# stm32-rs485-daughter.net
KiCad netlist of a schematic drawn in EAGLE
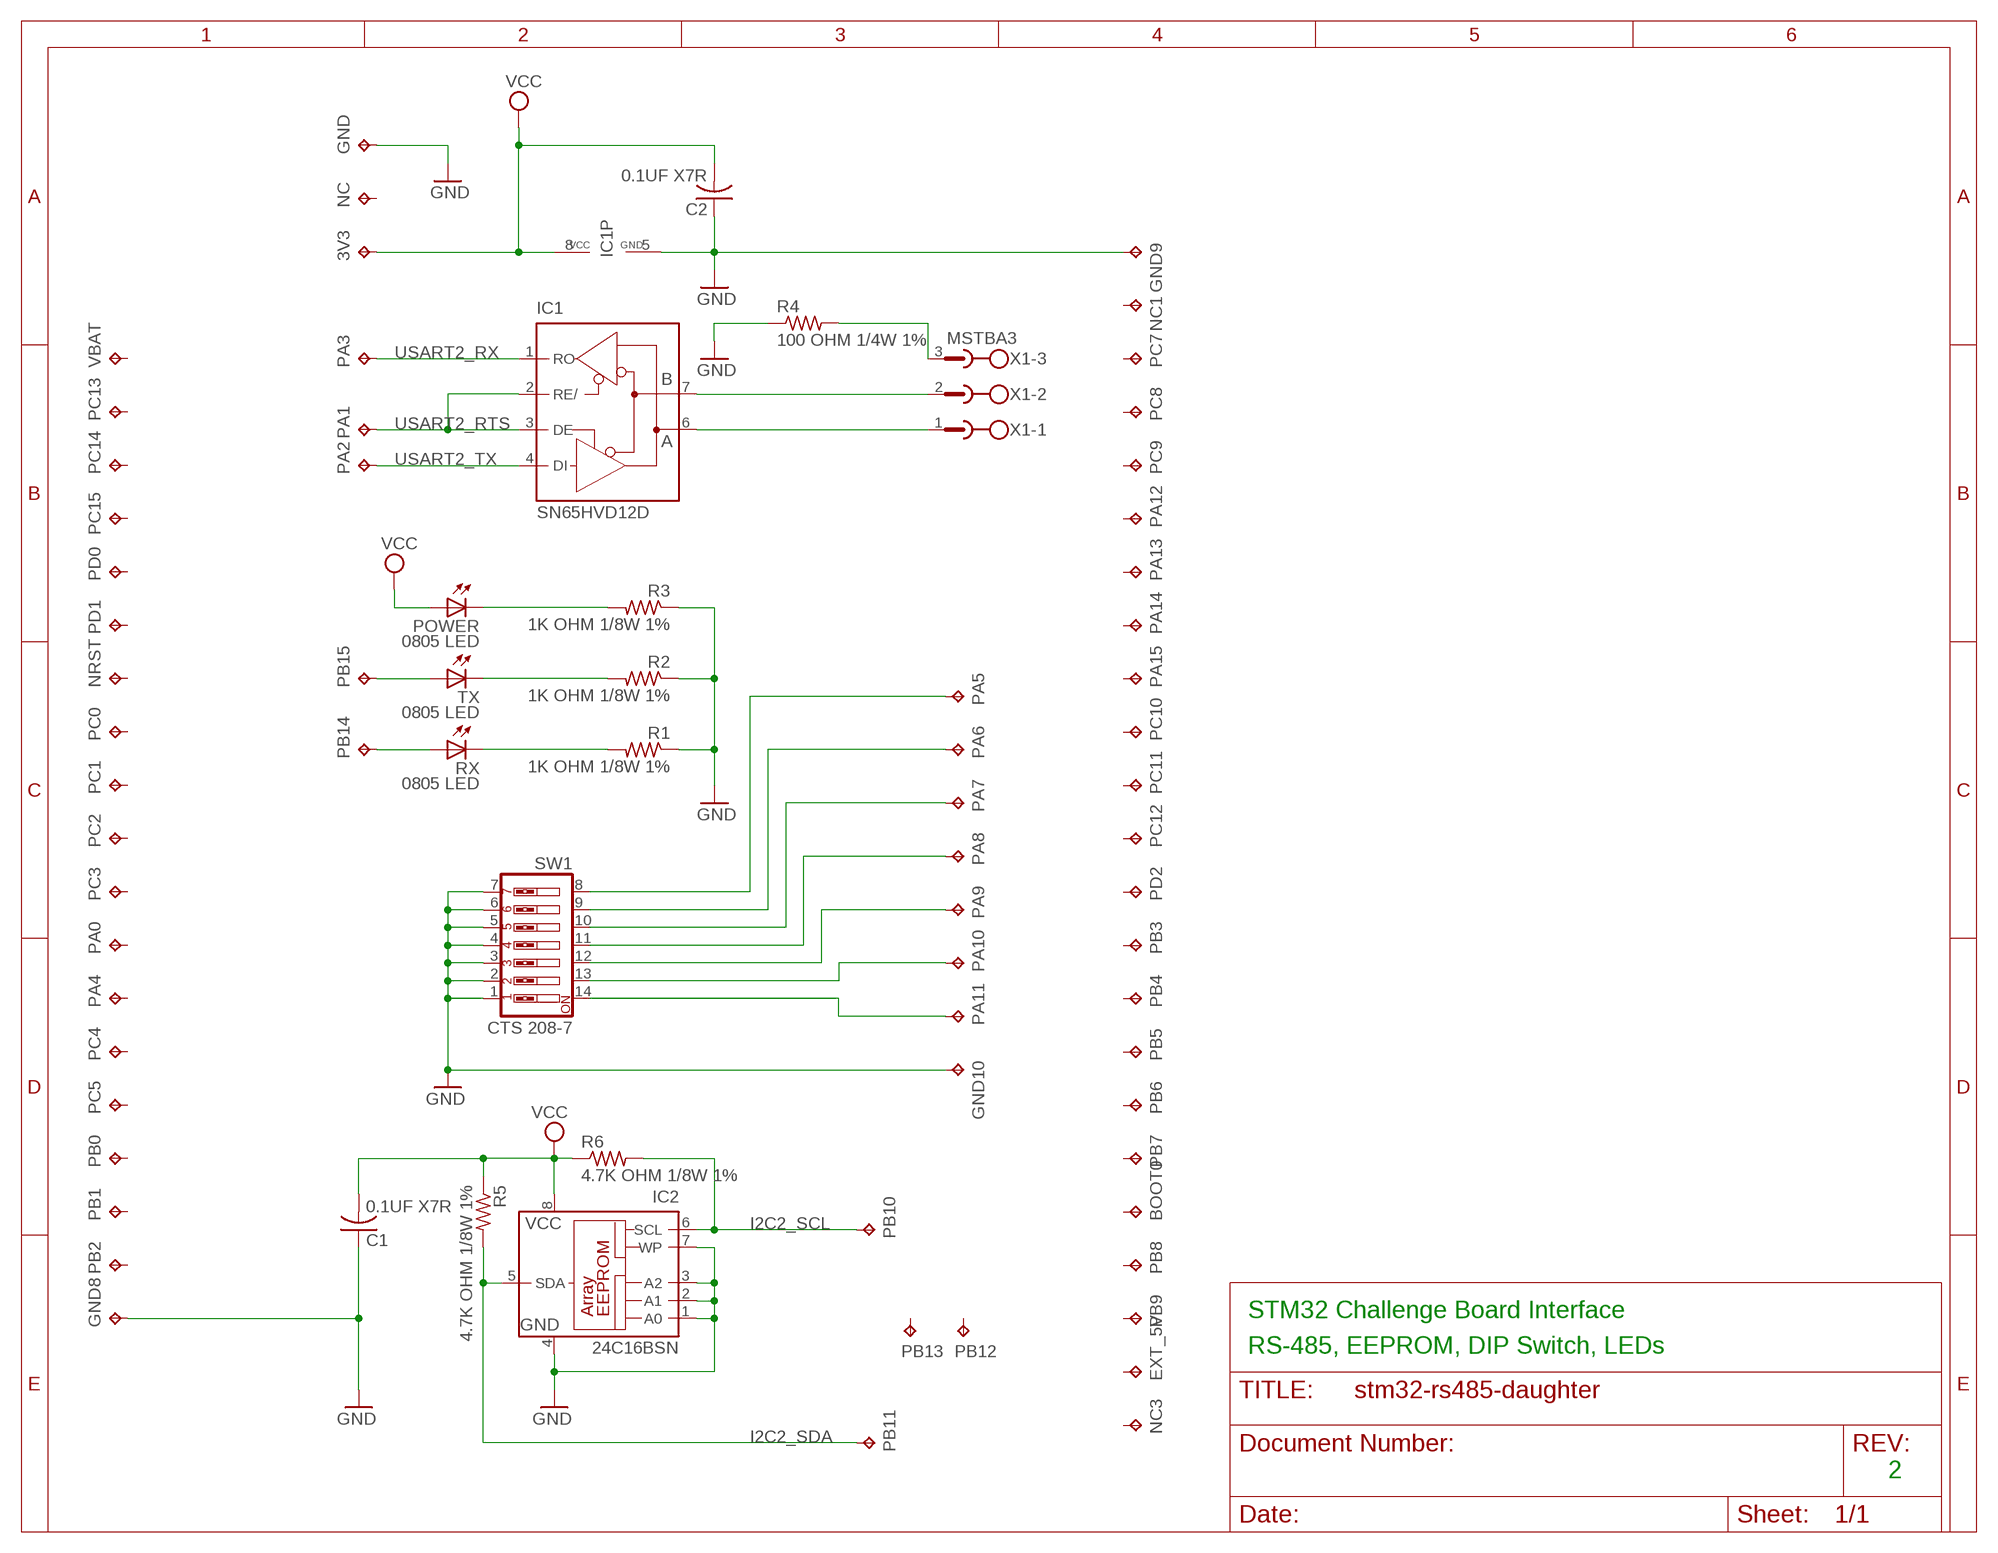
[diagram p0: schematic, sheet 1]

(export (version "E")
  (design (tool "Eeschema 10.0.6"))
  (components
    (comp (ref "3V3")
      (value "TPPAD1-13")
      (footprint "eagle-import:P1-13")
      (libsource (lib "eagle-import") (part "TPPAD1-13"))
    )
    (comp (ref "BOOT0")
      (value "TPPAD1-13")
      (footprint "eagle-import:P1-13")
      (libsource (lib "eagle-import") (part "TPPAD1-13"))
    )
    (comp (ref "C1")
      (value "0.1UF X7R")
      (footprint "eagle-import:C0805")
      (libsource (lib "eagle-import") (part "C-USC0805"))
    )
    (comp (ref "C2")
      (value "0.1UF X7R")
      (footprint "eagle-import:C0805")
      (libsource (lib "eagle-import") (part "C-USC0805"))
    )
    (comp (ref "EXT_5V")
      (value "TPPAD1-13")
      (footprint "eagle-import:P1-13")
      (libsource (lib "eagle-import") (part "TPPAD1-13"))
    )
    (comp (ref "GND")
      (value "TPPAD1-13")
      (footprint "eagle-import:P1-13")
      (libsource (lib "eagle-import") (part "TPPAD1-13"))
    )
    (comp (ref "GND8")
      (value "TPPAD1-13")
      (footprint "eagle-import:P1-13")
      (libsource (lib "eagle-import") (part "TPPAD1-13"))
    )
    (comp (ref "GND9")
      (value "TPPAD1-13")
      (footprint "eagle-import:P1-13")
      (libsource (lib "eagle-import") (part "TPPAD1-13"))
    )
    (comp (ref "GND10")
      (value "TPPAD1-13")
      (footprint "eagle-import:P1-13")
      (libsource (lib "eagle-import") (part "TPPAD1-13"))
    )
    (comp (ref "IC1")
      (value "SN65HVD12D")
      (footprint "eagle-import:SO08")
      (libsource (lib "eagle-import") (part "MAX481CSA"))
    )
    (comp (ref "IC2")
      (value "24C16BSN")
      (footprint "eagle-import:SO-08")
      (libsource (lib "eagle-import") (part "24SNC16B"))
    )
    (comp (ref "NC")
      (value "TPPAD1-13")
      (footprint "eagle-import:P1-13")
      (libsource (lib "eagle-import") (part "TPPAD1-13"))
    )
    (comp (ref "NC1")
      (value "TPPAD1-13")
      (footprint "eagle-import:P1-13")
      (libsource (lib "eagle-import") (part "TPPAD1-13"))
    )
    (comp (ref "NC3")
      (value "TPPAD1-13")
      (footprint "eagle-import:P1-13")
      (libsource (lib "eagle-import") (part "TPPAD1-13"))
    )
    (comp (ref "NRST")
      (value "TPPAD1-13")
      (footprint "eagle-import:P1-13")
      (libsource (lib "eagle-import") (part "TPPAD1-13"))
    )
    (comp (ref "PA0")
      (value "TPPAD1-13")
      (footprint "eagle-import:P1-13")
      (libsource (lib "eagle-import") (part "TPPAD1-13"))
    )
    (comp (ref "PA1")
      (value "TPPAD1-13")
      (footprint "eagle-import:P1-13")
      (libsource (lib "eagle-import") (part "TPPAD1-13"))
    )
    (comp (ref "PA2")
      (value "TPPAD1-13")
      (footprint "eagle-import:P1-13")
      (libsource (lib "eagle-import") (part "TPPAD1-13"))
    )
    (comp (ref "PA3")
      (value "TPPAD1-13")
      (footprint "eagle-import:P1-13")
      (libsource (lib "eagle-import") (part "TPPAD1-13"))
    )
    (comp (ref "PA4")
      (value "TPPAD1-13")
      (footprint "eagle-import:P1-13")
      (libsource (lib "eagle-import") (part "TPPAD1-13"))
    )
    (comp (ref "PA5")
      (value "TPPAD1-13")
      (footprint "eagle-import:P1-13")
      (libsource (lib "eagle-import") (part "TPPAD1-13"))
    )
    (comp (ref "PA6")
      (value "TPPAD1-13")
      (footprint "eagle-import:P1-13")
      (libsource (lib "eagle-import") (part "TPPAD1-13"))
    )
    (comp (ref "PA7")
      (value "TPPAD1-13")
      (footprint "eagle-import:P1-13")
      (libsource (lib "eagle-import") (part "TPPAD1-13"))
    )
    (comp (ref "PA8")
      (value "TPPAD1-13")
      (footprint "eagle-import:P1-13")
      (libsource (lib "eagle-import") (part "TPPAD1-13"))
    )
    (comp (ref "PA9")
      (value "TPPAD1-13")
      (footprint "eagle-import:P1-13")
      (libsource (lib "eagle-import") (part "TPPAD1-13"))
    )
    (comp (ref "PA10")
      (value "TPPAD1-13")
      (footprint "eagle-import:P1-13")
      (libsource (lib "eagle-import") (part "TPPAD1-13"))
    )
    (comp (ref "PA11")
      (value "TPPAD1-13")
      (footprint "eagle-import:P1-13")
      (libsource (lib "eagle-import") (part "TPPAD1-13"))
    )
    (comp (ref "PA12")
      (value "TPPAD1-13")
      (footprint "eagle-import:P1-13")
      (libsource (lib "eagle-import") (part "TPPAD1-13"))
    )
    (comp (ref "PA13")
      (value "TPPAD1-13")
      (footprint "eagle-import:P1-13")
      (libsource (lib "eagle-import") (part "TPPAD1-13"))
    )
    (comp (ref "PA14")
      (value "TPPAD1-13")
      (footprint "eagle-import:P1-13")
      (libsource (lib "eagle-import") (part "TPPAD1-13"))
    )
    (comp (ref "PA15")
      (value "TPPAD1-13")
      (footprint "eagle-import:P1-13")
      (libsource (lib "eagle-import") (part "TPPAD1-13"))
    )
    (comp (ref "PB0")
      (value "TPPAD1-13")
      (footprint "eagle-import:P1-13")
      (libsource (lib "eagle-import") (part "TPPAD1-13"))
    )
    (comp (ref "PB1")
      (value "TPPAD1-13")
      (footprint "eagle-import:P1-13")
      (libsource (lib "eagle-import") (part "TPPAD1-13"))
    )
    (comp (ref "PB2")
      (value "TPPAD1-13")
      (footprint "eagle-import:P1-13")
      (libsource (lib "eagle-import") (part "TPPAD1-13"))
    )
    (comp (ref "PB3")
      (value "TPPAD1-13")
      (footprint "eagle-import:P1-13")
      (libsource (lib "eagle-import") (part "TPPAD1-13"))
    )
    (comp (ref "PB4")
      (value "TPPAD1-13")
      (footprint "eagle-import:P1-13")
      (libsource (lib "eagle-import") (part "TPPAD1-13"))
    )
    (comp (ref "PB5")
      (value "TPPAD1-13")
      (footprint "eagle-import:P1-13")
      (libsource (lib "eagle-import") (part "TPPAD1-13"))
    )
    (comp (ref "PB6")
      (value "TPPAD1-13")
      (footprint "eagle-import:P1-13")
      (libsource (lib "eagle-import") (part "TPPAD1-13"))
    )
    (comp (ref "PB7")
      (value "TPPAD1-13")
      (footprint "eagle-import:P1-13")
      (libsource (lib "eagle-import") (part "TPPAD1-13"))
    )
    (comp (ref "PB8")
      (value "TPPAD1-13")
      (footprint "eagle-import:P1-13")
      (libsource (lib "eagle-import") (part "TPPAD1-13"))
    )
    (comp (ref "PB9")
      (value "TPPAD1-13")
      (footprint "eagle-import:P1-13")
      (libsource (lib "eagle-import") (part "TPPAD1-13"))
    )
    (comp (ref "PB10")
      (value "TPPAD1-13")
      (footprint "eagle-import:P1-13")
      (libsource (lib "eagle-import") (part "TPPAD1-13"))
    )
    (comp (ref "PB11")
      (value "TPPAD1-13")
      (footprint "eagle-import:P1-13")
      (libsource (lib "eagle-import") (part "TPPAD1-13"))
    )
    (comp (ref "PB12")
      (value "TPPAD1-13")
      (footprint "eagle-import:P1-13")
      (libsource (lib "eagle-import") (part "TPPAD1-13"))
    )
    (comp (ref "PB13")
      (value "TPPAD1-13")
      (footprint "eagle-import:P1-13")
      (libsource (lib "eagle-import") (part "TPPAD1-13"))
    )
    (comp (ref "PB14")
      (value "TPPAD1-13")
      (footprint "eagle-import:P1-13")
      (libsource (lib "eagle-import") (part "TPPAD1-13"))
    )
    (comp (ref "PB15")
      (value "TPPAD1-13")
      (footprint "eagle-import:P1-13")
      (libsource (lib "eagle-import") (part "TPPAD1-13"))
    )
    (comp (ref "PC0")
      (value "TPPAD1-13")
      (footprint "eagle-import:P1-13")
      (libsource (lib "eagle-import") (part "TPPAD1-13"))
    )
    (comp (ref "PC1")
      (value "TPPAD1-13")
      (footprint "eagle-import:P1-13")
      (libsource (lib "eagle-import") (part "TPPAD1-13"))
    )
    (comp (ref "PC2")
      (value "TPPAD1-13")
      (footprint "eagle-import:P1-13")
      (libsource (lib "eagle-import") (part "TPPAD1-13"))
    )
    (comp (ref "PC3")
      (value "TPPAD1-13")
      (footprint "eagle-import:P1-13")
      (libsource (lib "eagle-import") (part "TPPAD1-13"))
    )
    (comp (ref "PC4")
      (value "TPPAD1-13")
      (footprint "eagle-import:P1-13")
      (libsource (lib "eagle-import") (part "TPPAD1-13"))
    )
    (comp (ref "PC5")
      (value "TPPAD1-13")
      (footprint "eagle-import:P1-13")
      (libsource (lib "eagle-import") (part "TPPAD1-13"))
    )
    (comp (ref "PC7")
      (value "TPPAD1-13")
      (footprint "eagle-import:P1-13")
      (libsource (lib "eagle-import") (part "TPPAD1-13"))
    )
    (comp (ref "PC8")
      (value "TPPAD1-13")
      (footprint "eagle-import:P1-13")
      (libsource (lib "eagle-import") (part "TPPAD1-13"))
    )
    (comp (ref "PC9")
      (value "TPPAD1-13")
      (footprint "eagle-import:P1-13")
      (libsource (lib "eagle-import") (part "TPPAD1-13"))
    )
    (comp (ref "PC10")
      (value "TPPAD1-13")
      (footprint "eagle-import:P1-13")
      (libsource (lib "eagle-import") (part "TPPAD1-13"))
    )
    (comp (ref "PC11")
      (value "TPPAD1-13")
      (footprint "eagle-import:P1-13")
      (libsource (lib "eagle-import") (part "TPPAD1-13"))
    )
    (comp (ref "PC12")
      (value "TPPAD1-13")
      (footprint "eagle-import:P1-13")
      (libsource (lib "eagle-import") (part "TPPAD1-13"))
    )
    (comp (ref "PC13")
      (value "TPPAD1-13")
      (footprint "eagle-import:P1-13")
      (libsource (lib "eagle-import") (part "TPPAD1-13"))
    )
    (comp (ref "PC14")
      (value "TPPAD1-13")
      (footprint "eagle-import:P1-13")
      (libsource (lib "eagle-import") (part "TPPAD1-13"))
    )
    (comp (ref "PC15")
      (value "TPPAD1-13")
      (footprint "eagle-import:P1-13")
      (libsource (lib "eagle-import") (part "TPPAD1-13"))
    )
    (comp (ref "PD0")
      (value "TPPAD1-13")
      (footprint "eagle-import:P1-13")
      (libsource (lib "eagle-import") (part "TPPAD1-13"))
    )
    (comp (ref "PD1")
      (value "TPPAD1-13")
      (footprint "eagle-import:P1-13")
      (libsource (lib "eagle-import") (part "TPPAD1-13"))
    )
    (comp (ref "PD2")
      (value "TPPAD1-13")
      (footprint "eagle-import:P1-13")
      (libsource (lib "eagle-import") (part "TPPAD1-13"))
    )
    (comp (ref "POWER")
      (value "0805 LED")
      (footprint "eagle-import:CHIPLED_0805")
      (libsource (lib "eagle-import") (part "LEDCHIPLED_0805"))
    )
    (comp (ref "R1")
      (value "1K OHM 1/8W 1%")
      (footprint "eagle-import:R0805")
      (libsource (lib "eagle-import") (part "R-US_R0805"))
    )
    (comp (ref "R2")
      (value "1K OHM 1/8W 1%")
      (footprint "eagle-import:R0805")
      (libsource (lib "eagle-import") (part "R-US_R0805"))
    )
    (comp (ref "R3")
      (value "1K OHM 1/8W 1%")
      (footprint "eagle-import:R0805")
      (libsource (lib "eagle-import") (part "R-US_R0805"))
    )
    (comp (ref "R4")
      (value "100 OHM 1/4W 1%")
      (footprint "eagle-import:R1206")
      (libsource (lib "eagle-import") (part "R-US_R1206"))
    )
    (comp (ref "R5")
      (value "4.7K OHM 1/8W 1%")
      (footprint "eagle-import:R0805")
      (libsource (lib "eagle-import") (part "R-US_R0805"))
    )
    (comp (ref "R6")
      (value "4.7K OHM 1/8W 1%")
      (footprint "eagle-import:R0805")
      (libsource (lib "eagle-import") (part "R-US_R0805"))
    )
    (comp (ref "RX")
      (value "0805 LED")
      (footprint "eagle-import:CHIPLED_0805")
      (libsource (lib "eagle-import") (part "LEDCHIPLED_0805"))
    )
    (comp (ref "SW1")
      (value "CTS 208-7")
      (footprint "eagle-import:EDG-07")
      (libsource (lib "eagle-import") (part "SW_DIP-7"))
    )
    (comp (ref "TX")
      (value "0805 LED")
      (footprint "eagle-import:CHIPLED_0805")
      (libsource (lib "eagle-import") (part "LEDCHIPLED_0805"))
    )
    (comp (ref "VBAT")
      (value "TPPAD1-13")
      (footprint "eagle-import:P1-13")
      (libsource (lib "eagle-import") (part "TPPAD1-13"))
    )
    (comp (ref "X1")
      (value "MSTBA3")
      (footprint "eagle-import:MSTBA3")
      (libsource (lib "eagle-import") (part "MSTBA3"))
    )
  )
  (nets
    (net (code "1") (name "/I2C2_SCL") (class "Default")
      (node (ref "IC2") (pin "6") (pinfunction "SCL_6") (pintype "input"))
      (node (ref "PB10") (pin "TP") (pinfunction "TP_TP") (pintype "input"))
      (node (ref "R6") (pin "2") (pinfunction "2_2") (pintype "passive"))
    )
    (net (code "2") (name "/I2C2_SDA") (class "Default")
      (node (ref "IC2") (pin "5") (pinfunction "SDA_5") (pintype "bidirectional"))
      (node (ref "PB11") (pin "TP") (pinfunction "TP_TP") (pintype "input"))
      (node (ref "R5") (pin "2") (pinfunction "2_2") (pintype "passive"))
    )
    (net (code "3") (name "/USART2_RTS") (class "Default")
      (node (ref "IC1") (pin "2") (pinfunction "RE/_2") (pintype "input"))
      (node (ref "IC1") (pin "3") (pinfunction "DE_3") (pintype "input"))
      (node (ref "PA1") (pin "TP") (pinfunction "TP_TP") (pintype "input"))
    )
    (net (code "4") (name "/USART2_RX") (class "Default")
      (node (ref "IC1") (pin "1") (pinfunction "RO_1") (pintype "output"))
      (node (ref "PA3") (pin "TP") (pinfunction "TP_TP") (pintype "input"))
    )
    (net (code "5") (name "/USART2_TX") (class "Default")
      (node (ref "IC1") (pin "4") (pinfunction "DI_4") (pintype "input"))
      (node (ref "PA2") (pin "TP") (pinfunction "TP_TP") (pintype "input"))
    )
    (net (code "6") (name "GND") (class "Default")
      (node (ref "C1") (pin "1") (pinfunction "1_1") (pintype "passive"))
      (node (ref "C2") (pin "1") (pinfunction "1_1") (pintype "passive"))
      (node (ref "GND") (pin "TP") (pinfunction "TP_TP") (pintype "input"))
      (node (ref "GND10") (pin "TP") (pinfunction "TP_TP") (pintype "input"))
      (node (ref "GND8") (pin "TP") (pinfunction "TP_TP") (pintype "input"))
      (node (ref "GND9") (pin "TP") (pinfunction "TP_TP") (pintype "input"))
      (node (ref "IC1") (pin "5") (pinfunction "GND_5") (pintype "power_in"))
      (node (ref "IC2") (pin "1") (pinfunction "A0_1") (pintype "input"))
      (node (ref "IC2") (pin "2") (pinfunction "A1_2") (pintype "input"))
      (node (ref "IC2") (pin "3") (pinfunction "A2_3") (pintype "input"))
      (node (ref "IC2") (pin "4") (pinfunction "GND_4") (pintype "power_in"))
      (node (ref "IC2") (pin "7") (pinfunction "WP_7") (pintype "input"))
      (node (ref "R1") (pin "1") (pinfunction "1_1") (pintype "passive"))
      (node (ref "R2") (pin "1") (pinfunction "1_1") (pintype "passive"))
      (node (ref "R3") (pin "1") (pinfunction "1_1") (pintype "passive"))
      (node (ref "R4") (pin "1") (pinfunction "1_1") (pintype "passive"))
      (node (ref "SW1") (pin "1") (pinfunction "1_1") (pintype "passive"))
      (node (ref "SW1") (pin "2") (pinfunction "2_2") (pintype "passive"))
      (node (ref "SW1") (pin "3") (pinfunction "3_3") (pintype "passive"))
      (node (ref "SW1") (pin "4") (pinfunction "4_4") (pintype "passive"))
      (node (ref "SW1") (pin "5") (pinfunction "5_5") (pintype "passive"))
      (node (ref "SW1") (pin "6") (pinfunction "6_6") (pintype "passive"))
      (node (ref "SW1") (pin "7") (pinfunction "7_7") (pintype "passive"))
    )
    (net (code "7") (name "Net-(IC1A-A)") (class "Default")
      (node (ref "IC1") (pin "6") (pinfunction "A_6") (pintype "passive"))
      (node (ref "X1") (pin "1") (pinfunction "1_1") (pintype "passive"))
    )
    (net (code "8") (name "Net-(IC1A-B)") (class "Default")
      (node (ref "IC1") (pin "7") (pinfunction "B_7") (pintype "passive"))
      (node (ref "X1") (pin "2") (pinfunction "1_2") (pintype "passive"))
    )
    (net (code "9") (name "Net-(PA5-PadTP)") (class "Default")
      (node (ref "PA5") (pin "TP") (pinfunction "TP_TP") (pintype "input"))
      (node (ref "SW1") (pin "8") (pinfunction "8_8") (pintype "passive"))
    )
    (net (code "10") (name "Net-(PA6-PadTP)") (class "Default")
      (node (ref "PA6") (pin "TP") (pinfunction "TP_TP") (pintype "input"))
      (node (ref "SW1") (pin "9") (pinfunction "9_9") (pintype "passive"))
    )
    (net (code "11") (name "Net-(PA7-PadTP)") (class "Default")
      (node (ref "PA7") (pin "TP") (pinfunction "TP_TP") (pintype "input"))
      (node (ref "SW1") (pin "10") (pinfunction "10_10") (pintype "passive"))
    )
    (net (code "12") (name "Net-(PA8-PadTP)") (class "Default")
      (node (ref "PA8") (pin "TP") (pinfunction "TP_TP") (pintype "input"))
      (node (ref "SW1") (pin "11") (pinfunction "11_11") (pintype "passive"))
    )
    (net (code "13") (name "Net-(PA9-PadTP)") (class "Default")
      (node (ref "PA9") (pin "TP") (pinfunction "TP_TP") (pintype "input"))
      (node (ref "SW1") (pin "12") (pinfunction "12_12") (pintype "passive"))
    )
    (net (code "14") (name "Net-(PA10-PadTP)") (class "Default")
      (node (ref "PA10") (pin "TP") (pinfunction "TP_TP") (pintype "input"))
      (node (ref "SW1") (pin "13") (pinfunction "13_13") (pintype "passive"))
    )
    (net (code "15") (name "Net-(PA11-PadTP)") (class "Default")
      (node (ref "PA11") (pin "TP") (pinfunction "TP_TP") (pintype "input"))
      (node (ref "SW1") (pin "14") (pinfunction "14_14") (pintype "passive"))
    )
    (net (code "16") (name "Net-(PB14-PadTP)") (class "Default")
      (node (ref "PB14") (pin "TP") (pinfunction "TP_TP") (pintype "input"))
      (node (ref "RX") (pin "A") (pinfunction "A_A") (pintype "passive"))
    )
    (net (code "17") (name "Net-(PB15-PadTP)") (class "Default")
      (node (ref "PB15") (pin "TP") (pinfunction "TP_TP") (pintype "input"))
      (node (ref "TX") (pin "A") (pinfunction "A_A") (pintype "passive"))
    )
    (net (code "18") (name "Net-(POWER-PadC)") (class "Default")
      (node (ref "POWER") (pin "C") (pinfunction "C_C") (pintype "passive"))
      (node (ref "R3") (pin "2") (pinfunction "2_2") (pintype "passive"))
    )
    (net (code "19") (name "Net-(R1-Pad2)") (class "Default")
      (node (ref "R1") (pin "2") (pinfunction "2_2") (pintype "passive"))
      (node (ref "RX") (pin "C") (pinfunction "C_C") (pintype "passive"))
    )
    (net (code "20") (name "Net-(R2-Pad2)") (class "Default")
      (node (ref "R2") (pin "2") (pinfunction "2_2") (pintype "passive"))
      (node (ref "TX") (pin "C") (pinfunction "C_C") (pintype "passive"))
    )
    (net (code "21") (name "Net-(X1C-1)") (class "Default")
      (node (ref "R4") (pin "2") (pinfunction "2_2") (pintype "passive"))
      (node (ref "X1") (pin "3") (pinfunction "1_3") (pintype "passive"))
    )
    (net (code "22") (name "VCC") (class "Default")
      (node (ref "3V3") (pin "TP") (pinfunction "TP_TP") (pintype "input"))
      (node (ref "C1") (pin "2") (pinfunction "2_2") (pintype "passive"))
      (node (ref "C2") (pin "2") (pinfunction "2_2") (pintype "passive"))
      (node (ref "IC1") (pin "8") (pinfunction "VCC_8") (pintype "power_in"))
      (node (ref "IC2") (pin "8") (pinfunction "VCC_8") (pintype "power_in"))
      (node (ref "POWER") (pin "A") (pinfunction "A_A") (pintype "passive"))
      (node (ref "R5") (pin "1") (pinfunction "1_1") (pintype "passive"))
      (node (ref "R6") (pin "1") (pinfunction "1_1") (pintype "passive"))
    )
    (net (code "23") (name "unconnected-(BOOT0-PadTP)") (class "Default")
      (node (ref "BOOT0") (pin "TP") (pinfunction "TP_TP") (pintype "input"))
    )
    (net (code "24") (name "unconnected-(EXT_5V-PadTP)") (class "Default")
      (node (ref "EXT_5V") (pin "TP") (pinfunction "TP_TP") (pintype "input"))
    )
    (net (code "25") (name "unconnected-(NC-PadTP)") (class "Default")
      (node (ref "NC") (pin "TP") (pinfunction "TP_TP") (pintype "input"))
    )
    (net (code "26") (name "unconnected-(NC1-PadTP)") (class "Default")
      (node (ref "NC1") (pin "TP") (pinfunction "TP_TP") (pintype "input"))
    )
    (net (code "27") (name "unconnected-(NC3-PadTP)") (class "Default")
      (node (ref "NC3") (pin "TP") (pinfunction "TP_TP") (pintype "input"))
    )
    (net (code "28") (name "unconnected-(NRST-PadTP)") (class "Default")
      (node (ref "NRST") (pin "TP") (pinfunction "TP_TP") (pintype "input"))
    )
    (net (code "29") (name "unconnected-(PA0-PadTP)") (class "Default")
      (node (ref "PA0") (pin "TP") (pinfunction "TP_TP") (pintype "input"))
    )
    (net (code "30") (name "unconnected-(PA4-PadTP)") (class "Default")
      (node (ref "PA4") (pin "TP") (pinfunction "TP_TP") (pintype "input"))
    )
    (net (code "31") (name "unconnected-(PA12-PadTP)") (class "Default")
      (node (ref "PA12") (pin "TP") (pinfunction "TP_TP") (pintype "input"))
    )
    (net (code "32") (name "unconnected-(PA13-PadTP)") (class "Default")
      (node (ref "PA13") (pin "TP") (pinfunction "TP_TP") (pintype "input"))
    )
    (net (code "33") (name "unconnected-(PA14-PadTP)") (class "Default")
      (node (ref "PA14") (pin "TP") (pinfunction "TP_TP") (pintype "input"))
    )
    (net (code "34") (name "unconnected-(PA15-PadTP)") (class "Default")
      (node (ref "PA15") (pin "TP") (pinfunction "TP_TP") (pintype "input"))
    )
    (net (code "35") (name "unconnected-(PB0-PadTP)") (class "Default")
      (node (ref "PB0") (pin "TP") (pinfunction "TP_TP") (pintype "input"))
    )
    (net (code "36") (name "unconnected-(PB1-PadTP)") (class "Default")
      (node (ref "PB1") (pin "TP") (pinfunction "TP_TP") (pintype "input"))
    )
    (net (code "37") (name "unconnected-(PB2-PadTP)") (class "Default")
      (node (ref "PB2") (pin "TP") (pinfunction "TP_TP") (pintype "input"))
    )
    (net (code "38") (name "unconnected-(PB3-PadTP)") (class "Default")
      (node (ref "PB3") (pin "TP") (pinfunction "TP_TP") (pintype "input"))
    )
    (net (code "39") (name "unconnected-(PB4-PadTP)") (class "Default")
      (node (ref "PB4") (pin "TP") (pinfunction "TP_TP") (pintype "input"))
    )
    (net (code "40") (name "unconnected-(PB5-PadTP)") (class "Default")
      (node (ref "PB5") (pin "TP") (pinfunction "TP_TP") (pintype "input"))
    )
    (net (code "41") (name "unconnected-(PB6-PadTP)") (class "Default")
      (node (ref "PB6") (pin "TP") (pinfunction "TP_TP") (pintype "input"))
    )
    (net (code "42") (name "unconnected-(PB7-PadTP)") (class "Default")
      (node (ref "PB7") (pin "TP") (pinfunction "TP_TP") (pintype "input"))
    )
    (net (code "43") (name "unconnected-(PB8-PadTP)") (class "Default")
      (node (ref "PB8") (pin "TP") (pinfunction "TP_TP") (pintype "input"))
    )
    (net (code "44") (name "unconnected-(PB9-PadTP)") (class "Default")
      (node (ref "PB9") (pin "TP") (pinfunction "TP_TP") (pintype "input"))
    )
    (net (code "45") (name "unconnected-(PB12-PadTP)") (class "Default")
      (node (ref "PB12") (pin "TP") (pinfunction "TP_TP") (pintype "input"))
    )
    (net (code "46") (name "unconnected-(PB13-PadTP)") (class "Default")
      (node (ref "PB13") (pin "TP") (pinfunction "TP_TP") (pintype "input"))
    )
    (net (code "47") (name "unconnected-(PC0-PadTP)") (class "Default")
      (node (ref "PC0") (pin "TP") (pinfunction "TP_TP") (pintype "input"))
    )
    (net (code "48") (name "unconnected-(PC1-PadTP)") (class "Default")
      (node (ref "PC1") (pin "TP") (pinfunction "TP_TP") (pintype "input"))
    )
    (net (code "49") (name "unconnected-(PC2-PadTP)") (class "Default")
      (node (ref "PC2") (pin "TP") (pinfunction "TP_TP") (pintype "input"))
    )
    (net (code "50") (name "unconnected-(PC3-PadTP)") (class "Default")
      (node (ref "PC3") (pin "TP") (pinfunction "TP_TP") (pintype "input"))
    )
    (net (code "51") (name "unconnected-(PC4-PadTP)") (class "Default")
      (node (ref "PC4") (pin "TP") (pinfunction "TP_TP") (pintype "input"))
    )
    (net (code "52") (name "unconnected-(PC5-PadTP)") (class "Default")
      (node (ref "PC5") (pin "TP") (pinfunction "TP_TP") (pintype "input"))
    )
    (net (code "53") (name "unconnected-(PC7-PadTP)") (class "Default")
      (node (ref "PC7") (pin "TP") (pinfunction "TP_TP") (pintype "input"))
    )
    (net (code "54") (name "unconnected-(PC8-PadTP)") (class "Default")
      (node (ref "PC8") (pin "TP") (pinfunction "TP_TP") (pintype "input"))
    )
    (net (code "55") (name "unconnected-(PC9-PadTP)") (class "Default")
      (node (ref "PC9") (pin "TP") (pinfunction "TP_TP") (pintype "input"))
    )
    (net (code "56") (name "unconnected-(PC10-PadTP)") (class "Default")
      (node (ref "PC10") (pin "TP") (pinfunction "TP_TP") (pintype "input"))
    )
    (net (code "57") (name "unconnected-(PC11-PadTP)") (class "Default")
      (node (ref "PC11") (pin "TP") (pinfunction "TP_TP") (pintype "input"))
    )
    (net (code "58") (name "unconnected-(PC12-PadTP)") (class "Default")
      (node (ref "PC12") (pin "TP") (pinfunction "TP_TP") (pintype "input"))
    )
    (net (code "59") (name "unconnected-(PC13-PadTP)") (class "Default")
      (node (ref "PC13") (pin "TP") (pinfunction "TP_TP") (pintype "input"))
    )
    (net (code "60") (name "unconnected-(PC14-PadTP)") (class "Default")
      (node (ref "PC14") (pin "TP") (pinfunction "TP_TP") (pintype "input"))
    )
    (net (code "61") (name "unconnected-(PC15-PadTP)") (class "Default")
      (node (ref "PC15") (pin "TP") (pinfunction "TP_TP") (pintype "input"))
    )
    (net (code "62") (name "unconnected-(PD0-PadTP)") (class "Default")
      (node (ref "PD0") (pin "TP") (pinfunction "TP_TP") (pintype "input"))
    )
    (net (code "63") (name "unconnected-(PD1-PadTP)") (class "Default")
      (node (ref "PD1") (pin "TP") (pinfunction "TP_TP") (pintype "input"))
    )
    (net (code "64") (name "unconnected-(PD2-PadTP)") (class "Default")
      (node (ref "PD2") (pin "TP") (pinfunction "TP_TP") (pintype "input"))
    )
    (net (code "65") (name "unconnected-(VBAT-PadTP)") (class "Default")
      (node (ref "VBAT") (pin "TP") (pinfunction "TP_TP") (pintype "input"))
    )
  )
)
